# PoE_Front_End_FE.net
KiCad netlist of a schematic drawn in Altium Designer
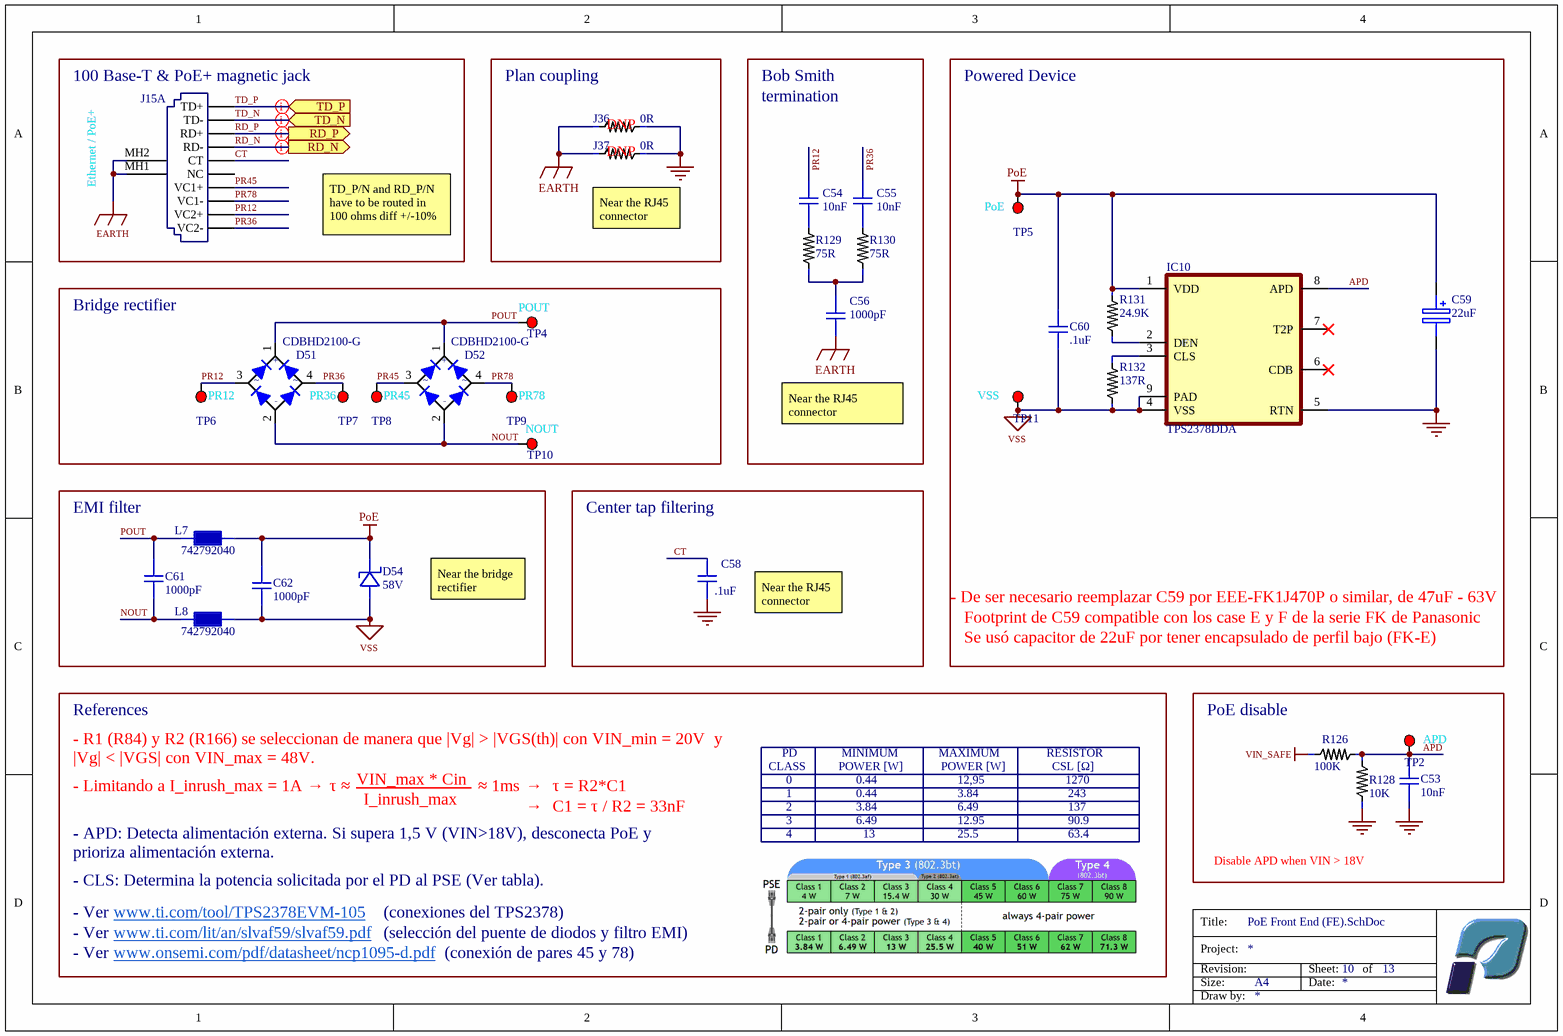
[diagram p0: PoE Front End (FE).SchDoc]

(export (version "E")
  (design (tool "Eeschema 10.0.6"))
  (components
    (comp (ref "C53")
      (value "10nF")
      (footprint "C0805")
      (description "Multilayer Ceramic Capacitors MLCC - SMD/SMT 100V 0.01uF X7R 0805 10%")
      (fields (field (name "PART NUMBER") "C0805C103K1RACTU") (field (name "MANUFACTURER") "KEMET"))
      (libsource (lib "SCH-LIB-V2") (part "C-10nF-100V-0805"))
    )
    (comp (ref "C54")
      (value "10nF")
      (footprint "C0805")
      (description "Multilayer Ceramic Capacitors MLCC - SMD/SMT 100V 0.01uF X7R 0805 10%")
      (fields (field (name "PART NUMBER") "C0805C103K1RACTU") (field (name "MANUFACTURER") "KEMET"))
      (libsource (lib "SCH-LIB-V2") (part "C-10nF-100V-0805"))
    )
    (comp (ref "C55")
      (value "10nF")
      (footprint "C0805")
      (description "Multilayer Ceramic Capacitors MLCC - SMD/SMT 100V 0.01uF X7R 0805 10%")
      (fields (field (name "PART NUMBER") "C0805C103K1RACTU") (field (name "MANUFACTURER") "KEMET"))
      (libsource (lib "SCH-LIB-V2") (part "C-10nF-100V-0805"))
    )
    (comp (ref "C56")
      (value "1000pF")
      (footprint "C1206")
      (description "Multilayer Ceramic Capacitors MLCC - SMD/SMT 2kV 1000pF X7R 1206 10%")
      (fields (field (name "PART NUMBER") "C1206C102KGRACTU") (field (name "MANUFACTURER") "KEMET"))
      (libsource (lib "SCH-LIB-V2") (part "C-1000pF-2kV-1206"))
    )
    (comp (ref "C58")
      (value ".1uF")
      (footprint "C0805")
      (description "Multilayer Ceramic Capacitors MLCC - SMD/SMT 16V 0.1uF X7R 0805 10%")
      (fields (field (name "PART NUMBER") "C0805C104K4RACTU") (field (name "MANUFACTURER") "KEMET"))
      (libsource (lib "SCH-LIB-V2") (part "C-0.1uF-16V-0805"))
    )
    (comp (ref "C59")
      (value "22uF")
      (footprint "C-FK-E")
      (description "Aluminum Electrolytic Capacitors - SMD 22uF 63V")
      (fields (field (name "MANUFACTURER") "Panasonic") (field (name "PART NUMBER") "EEE-FK1J220P"))
      (libsource (lib "SCH-LIB-V2") (part "C-22uF-63V"))
    )
    (comp (ref "C60")
      (value ".1uF")
      (footprint "C0805")
      (description "Multilayer Ceramic Capacitors MLCC - SMD/SMT 100V 0.1uF X7R 0805 10%")
      (fields (field (name "PART NUMBER") "C0805C104K1RACTU") (field (name "MANUFACTURER") "KEMET"))
      (libsource (lib "SCH-LIB-V2") (part "C-0.1uF-100V-0805"))
    )
    (comp (ref "C61")
      (value "1000pF")
      (footprint "C0805")
      (description "Multilayer Ceramic Capacitors MLCC - SMD/SMT 100V 1000pF X7R 0805 10%")
      (fields (field (name "PART NUMBER") "C0805C102K1RACTU") (field (name "MANUFACTURER") "KEMET"))
      (libsource (lib "SCH-LIB-V2") (part "C-1000pF-100V-0805"))
    )
    (comp (ref "C62")
      (value "1000pF")
      (footprint "C0805")
      (description "Multilayer Ceramic Capacitors MLCC - SMD/SMT 100V 1000pF X7R 0805 10%")
      (fields (field (name "PART NUMBER") "C0805C102K1RACTU") (field (name "MANUFACTURER") "KEMET"))
      (libsource (lib "SCH-LIB-V2") (part "C-1000pF-100V-0805"))
    )
    (comp (ref "D51")
      (value "Bridge Rectifier")
      (footprint "TO-269AA-4")
      (description "Bridge Rectifiers 2A 100V Schottky Bridge")
      (fields (field (name "MANUFACTURER") "Comchip Technology") (field (name "PART NUMBER") "CDBHD2100-G"))
      (libsource (lib "SCH-LIB-V2") (part "D-CDBHD2100-G"))
    )
    (comp (ref "D52")
      (value "Bridge Rectifier")
      (footprint "TO-269AA-4")
      (description "Bridge Rectifiers 2A 100V Schottky Bridge")
      (fields (field (name "MANUFACTURER") "Comchip Technology") (field (name "PART NUMBER") "CDBHD2100-G"))
      (libsource (lib "SCH-LIB-V2") (part "D-CDBHD2100-G"))
    )
    (comp (ref "D54")
      (value "58V")
      (footprint "SOD-123")
      (description "ESD Protection Diodes / TVS Diodes 200W 58V 5% Uni-directional")
      (fields (field (name "PART NUMBER") "SMF58A") (field (name "MANUFACTURER") "Littelfuse"))
      (libsource (lib "SCH-LIB-V2") (part "D-TVS-58V-SOD123"))
    )
    (comp (ref "IC10")
      (value "PD interface")
      (footprint "HSOP-8")
      (description "IEEE 802.3at PoE High-Power PD Interface")
      (fields (field (name "MANUFACTURER") "Texas Instruments") (field (name "PART NUMBER") "TPS2378DDA"))
      (libsource (lib "SCH-LIB-V2") (part "IC-TPS2378"))
    )
    (comp (ref "J15")
      (value "Magnetic Jack")
      (footprint "J-ARJM11C7-104-AB-EW2")
      (fields (field (name "MANUFACTURER") "ABRACOM") (field (name "PART NUMBER") "ARJM11C7-104-AB-EW2"))
      (libsource (lib "SCH-LIB-V2") (part "J-ARJM11C7-104-AB-EW2"))
    )
    (comp (ref "J36")
      (value "0R")
      (footprint "J0805")
      (description "Solder Bridge 0805 ON")
      (fields (field (name "PART NUMBER") "RC0805FR-070RL") (field (name "MANUFACTURER") "YAGEO"))
      (libsource (lib "SCH-LIB-V2") (part "J-0805"))
    )
    (comp (ref "J37")
      (value "0R")
      (footprint "J0805")
      (description "Solder Bridge 0805 ON")
      (fields (field (name "PART NUMBER") "RC0805FR-070RL") (field (name "MANUFACTURER") "YAGEO"))
      (libsource (lib "SCH-LIB-V2") (part "J-0805"))
    )
    (comp (ref "L7")
      (value "Ferrite Beads")
      (footprint "L0805")
      (description "Ferrite Beads 600Ohm 2000mA Impedance@100MHz 0805")
      (fields (field (name "MANUFACTURER") "Wurth Elektronik") (field (name "PART NUMBER") "742792040"))
      (libsource (lib "SCH-LIB-V2") (part "L-600R-2A-0805"))
    )
    (comp (ref "L8")
      (value "Ferrite Beads")
      (footprint "L0805")
      (description "Ferrite Beads 600Ohm 2000mA Impedance@100MHz 0805")
      (fields (field (name "MANUFACTURER") "Wurth Elektronik") (field (name "PART NUMBER") "742792040"))
      (libsource (lib "SCH-LIB-V2") (part "L-600R-2A-0805"))
    )
    (comp (ref "R126")
      (value "100K")
      (footprint "R0805")
      (description "Thick Film Resistors - SMD 100 kOhms 125 mW 0805 1%")
      (fields (field (name "PART NUMBER") "RC0805FR-07100KL") (field (name "MANUFACTURER") "YAGEO"))
      (libsource (lib "SCH-LIB-V2") (part "R-100K-1%-0805"))
    )
    (comp (ref "R128")
      (value "10K")
      (footprint "R0805")
      (description "Thick Film Resistors - SMD 10 kOhms 125 mW 0805 1%")
      (fields (field (name "PART NUMBER") "RC0805FR-0710KL") (field (name "MANUFACTURER") "YAGEO"))
      (libsource (lib "SCH-LIB-V2") (part "R-10K-1%-0805"))
    )
    (comp (ref "R129")
      (value "75R")
      (footprint "R0805")
      (description "Thick Film Resistors - SMD 75 Ohms 125 mW 0805 1%")
      (fields (field (name "PART NUMBER") "RC0805FR-0775RL") (field (name "MANUFACTURER") "YAGEO"))
      (libsource (lib "SCH-LIB-V2") (part "R-75R-1%-0805"))
    )
    (comp (ref "R130")
      (value "75R")
      (footprint "R0805")
      (description "Thick Film Resistors - SMD 75 Ohms 125 mW 0805 1%")
      (fields (field (name "PART NUMBER") "RC0805FR-0775RL") (field (name "MANUFACTURER") "YAGEO"))
      (libsource (lib "SCH-LIB-V2") (part "R-75R-1%-0805"))
    )
    (comp (ref "R131")
      (value "24.9K")
      (footprint "R0805")
      (description "Thick Film Resistors - SMD 24.9 kOhms 125 mW 0805 1%")
      (fields (field (name "PART NUMBER") "RC0805FR-0724K9L") (field (name "MANUFACTURER") "YAGEO"))
      (libsource (lib "SCH-LIB-V2") (part "R-24K9-1%-0805"))
    )
    (comp (ref "R132")
      (value "137R")
      (footprint "R0805")
      (description "Thick Film Resistors - SMD 137 Ohms 125 mW 0805 1%")
      (fields (field (name "PART NUMBER") "RC0805FR-07137RL") (field (name "MANUFACTURER") "YAGEO"))
      (libsource (lib "SCH-LIB-V2") (part "R-137R-1%-0805"))
    )
    (comp (ref "TP2")
      (value "Test point")
      (footprint "TP-1MM")
      (description "Test Plugs & Test Jacks")
      (libsource (lib "SCH-LIB-V2") (part "TP-1MM"))
    )
    (comp (ref "TP4")
      (value "Test point")
      (footprint "TP-1MM")
      (description "Test Plugs & Test Jacks")
      (libsource (lib "SCH-LIB-V2") (part "TP-1MM"))
    )
    (comp (ref "TP5")
      (value "Test point")
      (footprint "TP-1MM")
      (description "Test Plugs & Test Jacks")
      (libsource (lib "SCH-LIB-V2") (part "TP-1MM"))
    )
    (comp (ref "TP6")
      (value "Test point")
      (footprint "TP-1MM")
      (description "Test Plugs & Test Jacks")
      (libsource (lib "SCH-LIB-V2") (part "TP-1MM"))
    )
    (comp (ref "TP7")
      (value "Test point")
      (footprint "TP-1MM")
      (description "Test Plugs & Test Jacks")
      (libsource (lib "SCH-LIB-V2") (part "TP-1MM"))
    )
    (comp (ref "TP8")
      (value "Test point")
      (footprint "TP-1MM")
      (description "Test Plugs & Test Jacks")
      (libsource (lib "SCH-LIB-V2") (part "TP-1MM"))
    )
    (comp (ref "TP9")
      (value "Test point")
      (footprint "TP-1MM")
      (description "Test Plugs & Test Jacks")
      (libsource (lib "SCH-LIB-V2") (part "TP-1MM"))
    )
    (comp (ref "TP10")
      (value "Test point")
      (footprint "TP-1MM")
      (description "Test Plugs & Test Jacks")
      (libsource (lib "SCH-LIB-V2") (part "TP-1MM"))
    )
    (comp (ref "TP11")
      (value "Test point")
      (footprint "TP-1MM")
      (description "Test Plugs & Test Jacks")
      (libsource (lib "SCH-LIB-V2") (part "TP-1MM"))
    )
  )
  (nets
    (net (code "1") (name "/APD") (class "Default")
      (node (ref "C53") (pin "1") (pinfunction "1_1") (pintype "passive"))
      (node (ref "IC10") (pin "8") (pinfunction "APD_8") (pintype "passive"))
      (node (ref "R126") (pin "2") (pinfunction "2_2") (pintype "passive"))
      (node (ref "R128") (pin "2") (pinfunction "2_2") (pintype "passive"))
      (node (ref "TP2") (pin "1") (pinfunction "1_1") (pintype "passive"))
    )
    (net (code "2") (name "/CT") (class "Default")
      (node (ref "C58") (pin "1") (pinfunction "1_1") (pintype "passive"))
      (node (ref "J15") (pin "5") (pinfunction "CT_5") (pintype "passive"))
    )
    (net (code "3") (name "/NOUT") (class "Default")
      (node (ref "C61") (pin "2") (pinfunction "2_2") (pintype "passive"))
      (node (ref "D51") (pin "2") (pinfunction "-_2") (pintype "passive"))
      (node (ref "D52") (pin "2") (pinfunction "-_2") (pintype "passive"))
      (node (ref "L8") (pin "1") (pinfunction "1_1") (pintype "passive"))
      (node (ref "TP10") (pin "1") (pinfunction "1_1") (pintype "passive"))
    )
    (net (code "4") (name "/POUT") (class "Default")
      (node (ref "C61") (pin "1") (pinfunction "1_1") (pintype "passive"))
      (node (ref "D51") (pin "1") (pinfunction "+_1") (pintype "passive"))
      (node (ref "D52") (pin "1") (pinfunction "+_1") (pintype "passive"))
      (node (ref "L7") (pin "1") (pinfunction "1_1") (pintype "passive"))
      (node (ref "TP4") (pin "1") (pinfunction "1_1") (pintype "passive"))
    )
    (net (code "5") (name "/PR12") (class "Default")
      (node (ref "C54") (pin "1") (pinfunction "1_1") (pintype "passive"))
      (node (ref "D51") (pin "3") (pinfunction "~_3") (pintype "passive"))
      (node (ref "J15") (pin "9") (pinfunction "VC2+_9") (pintype "passive"))
      (node (ref "TP6") (pin "1") (pinfunction "1_1") (pintype "passive"))
    )
    (net (code "6") (name "/PR36") (class "Default")
      (node (ref "C55") (pin "1") (pinfunction "1_1") (pintype "passive"))
      (node (ref "D51") (pin "4") (pinfunction "~_4") (pintype "passive"))
      (node (ref "J15") (pin "10") (pinfunction "VC2-_10") (pintype "passive"))
      (node (ref "TP7") (pin "1") (pinfunction "1_1") (pintype "passive"))
    )
    (net (code "7") (name "/PR45") (class "Default")
      (node (ref "D52") (pin "3") (pinfunction "~_3") (pintype "passive"))
      (node (ref "J15") (pin "7") (pinfunction "VC1+_7") (pintype "passive"))
      (node (ref "TP8") (pin "1") (pinfunction "1_1") (pintype "passive"))
    )
    (net (code "8") (name "/PR78") (class "Default")
      (node (ref "D52") (pin "4") (pinfunction "~_4") (pintype "passive"))
      (node (ref "J15") (pin "8") (pinfunction "VC1-_8") (pintype "passive"))
      (node (ref "TP9") (pin "1") (pinfunction "1_1") (pintype "passive"))
    )
    (net (code "9") (name "/RD_N") (class "Default")
      (node (ref "J15") (pin "4") (pinfunction "RD-_4") (pintype "passive"))
    )
    (net (code "10") (name "/RD_P") (class "Default")
      (node (ref "J15") (pin "3") (pinfunction "RD+_3") (pintype "passive"))
    )
    (net (code "11") (name "/TD_N") (class "Default")
      (node (ref "J15") (pin "2") (pinfunction "TD-_2") (pintype "passive"))
    )
    (net (code "12") (name "/TD_P") (class "Default")
      (node (ref "J15") (pin "1") (pinfunction "TD+_1") (pintype "passive"))
    )
    (net (code "13") (name "EARTH") (class "Default")
      (node (ref "C56") (pin "2") (pinfunction "2_2") (pintype "passive"))
      (node (ref "J15") (pin "MH1") (pinfunction "MH1_MH1") (pintype "passive"))
      (node (ref "J15") (pin "MH2") (pinfunction "MH2_MH2") (pintype "passive"))
      (node (ref "J36") (pin "1") (pinfunction "1_1") (pintype "passive"))
      (node (ref "J37") (pin "1") (pinfunction "1_1") (pintype "passive"))
    )
    (net (code "14") (name "GND") (class "Default")
      (node (ref "C53") (pin "2") (pinfunction "2_2") (pintype "passive"))
      (node (ref "C58") (pin "2") (pinfunction "2_2") (pintype "passive"))
      (node (ref "C59") (pin "2") (pinfunction "-_2") (pintype "passive"))
      (node (ref "IC10") (pin "5") (pinfunction "RTN_5") (pintype "passive"))
      (node (ref "J36") (pin "2") (pinfunction "2_2") (pintype "passive"))
      (node (ref "J37") (pin "2") (pinfunction "2_2") (pintype "passive"))
      (node (ref "R128") (pin "1") (pinfunction "1_1") (pintype "passive"))
    )
    (net (code "15") (name "Net-(C54-Pad2)") (class "Default")
      (node (ref "C54") (pin "2") (pinfunction "2_2") (pintype "passive"))
      (node (ref "R129") (pin "2") (pinfunction "2_2") (pintype "passive"))
    )
    (net (code "16") (name "Net-(C55-Pad2)") (class "Default")
      (node (ref "C55") (pin "2") (pinfunction "2_2") (pintype "passive"))
      (node (ref "R130") (pin "2") (pinfunction "2_2") (pintype "passive"))
    )
    (net (code "17") (name "Net-(C56-Pad1)") (class "Default")
      (node (ref "C56") (pin "1") (pinfunction "1_1") (pintype "passive"))
      (node (ref "R129") (pin "1") (pinfunction "1_1") (pintype "passive"))
      (node (ref "R130") (pin "1") (pinfunction "1_1") (pintype "passive"))
    )
    (net (code "18") (name "Net-(IC10-CLS)") (class "Default")
      (node (ref "IC10") (pin "3") (pinfunction "CLS_3") (pintype "passive"))
      (node (ref "R132") (pin "2") (pinfunction "2_2") (pintype "passive"))
    )
    (net (code "19") (name "Net-(IC10-DEN)") (class "Default")
      (node (ref "IC10") (pin "2") (pinfunction "DEN_2") (pintype "passive"))
      (node (ref "R131") (pin "1") (pinfunction "1_1") (pintype "passive"))
    )
    (net (code "20") (name "PoE") (class "Default")
      (node (ref "C59") (pin "1") (pinfunction "+_1") (pintype "passive"))
      (node (ref "C60") (pin "1") (pinfunction "1_1") (pintype "passive"))
      (node (ref "C62") (pin "1") (pinfunction "1_1") (pintype "passive"))
      (node (ref "D54") (pin "1") (pinfunction "1_1") (pintype "passive"))
      (node (ref "IC10") (pin "1") (pinfunction "VDD_1") (pintype "passive"))
      (node (ref "L7") (pin "2") (pinfunction "2_2") (pintype "passive"))
      (node (ref "R131") (pin "2") (pinfunction "2_2") (pintype "passive"))
      (node (ref "TP5") (pin "1") (pinfunction "1_1") (pintype "passive"))
    )
    (net (code "21") (name "VIN_SAFE") (class "Default")
      (node (ref "R126") (pin "1") (pinfunction "1_1") (pintype "passive"))
    )
    (net (code "22") (name "VSS") (class "Default")
      (node (ref "C60") (pin "2") (pinfunction "2_2") (pintype "passive"))
      (node (ref "C62") (pin "2") (pinfunction "2_2") (pintype "passive"))
      (node (ref "D54") (pin "2") (pinfunction "2_2") (pintype "passive"))
      (node (ref "IC10") (pin "4") (pinfunction "VSS_4") (pintype "passive"))
      (node (ref "IC10") (pin "9") (pinfunction "PAD_9") (pintype "passive"))
      (node (ref "L8") (pin "2") (pinfunction "2_2") (pintype "passive"))
      (node (ref "R132") (pin "1") (pinfunction "1_1") (pintype "passive"))
      (node (ref "TP11") (pin "1") (pinfunction "1_1") (pintype "passive"))
    )
    (net (code "23") (name "unconnected-(IC10-CDB-Pad6)") (class "Default")
      (node (ref "IC10") (pin "6") (pinfunction "CDB_6") (pintype "passive+no_connect"))
    )
    (net (code "24") (name "unconnected-(IC10-T2P-Pad7)") (class "Default")
      (node (ref "IC10") (pin "7") (pinfunction "T2P_7") (pintype "passive+no_connect"))
    )
    (net (code "25") (name "unconnected-(J15A-NC-Pad6)") (class "Default")
      (node (ref "J15") (pin "6") (pinfunction "NC_6") (pintype "passive"))
    )
  )
)
